# SCH_CarPCB_2023-11-15.net
KiCad netlist of a schematic drawn in EasyEDA
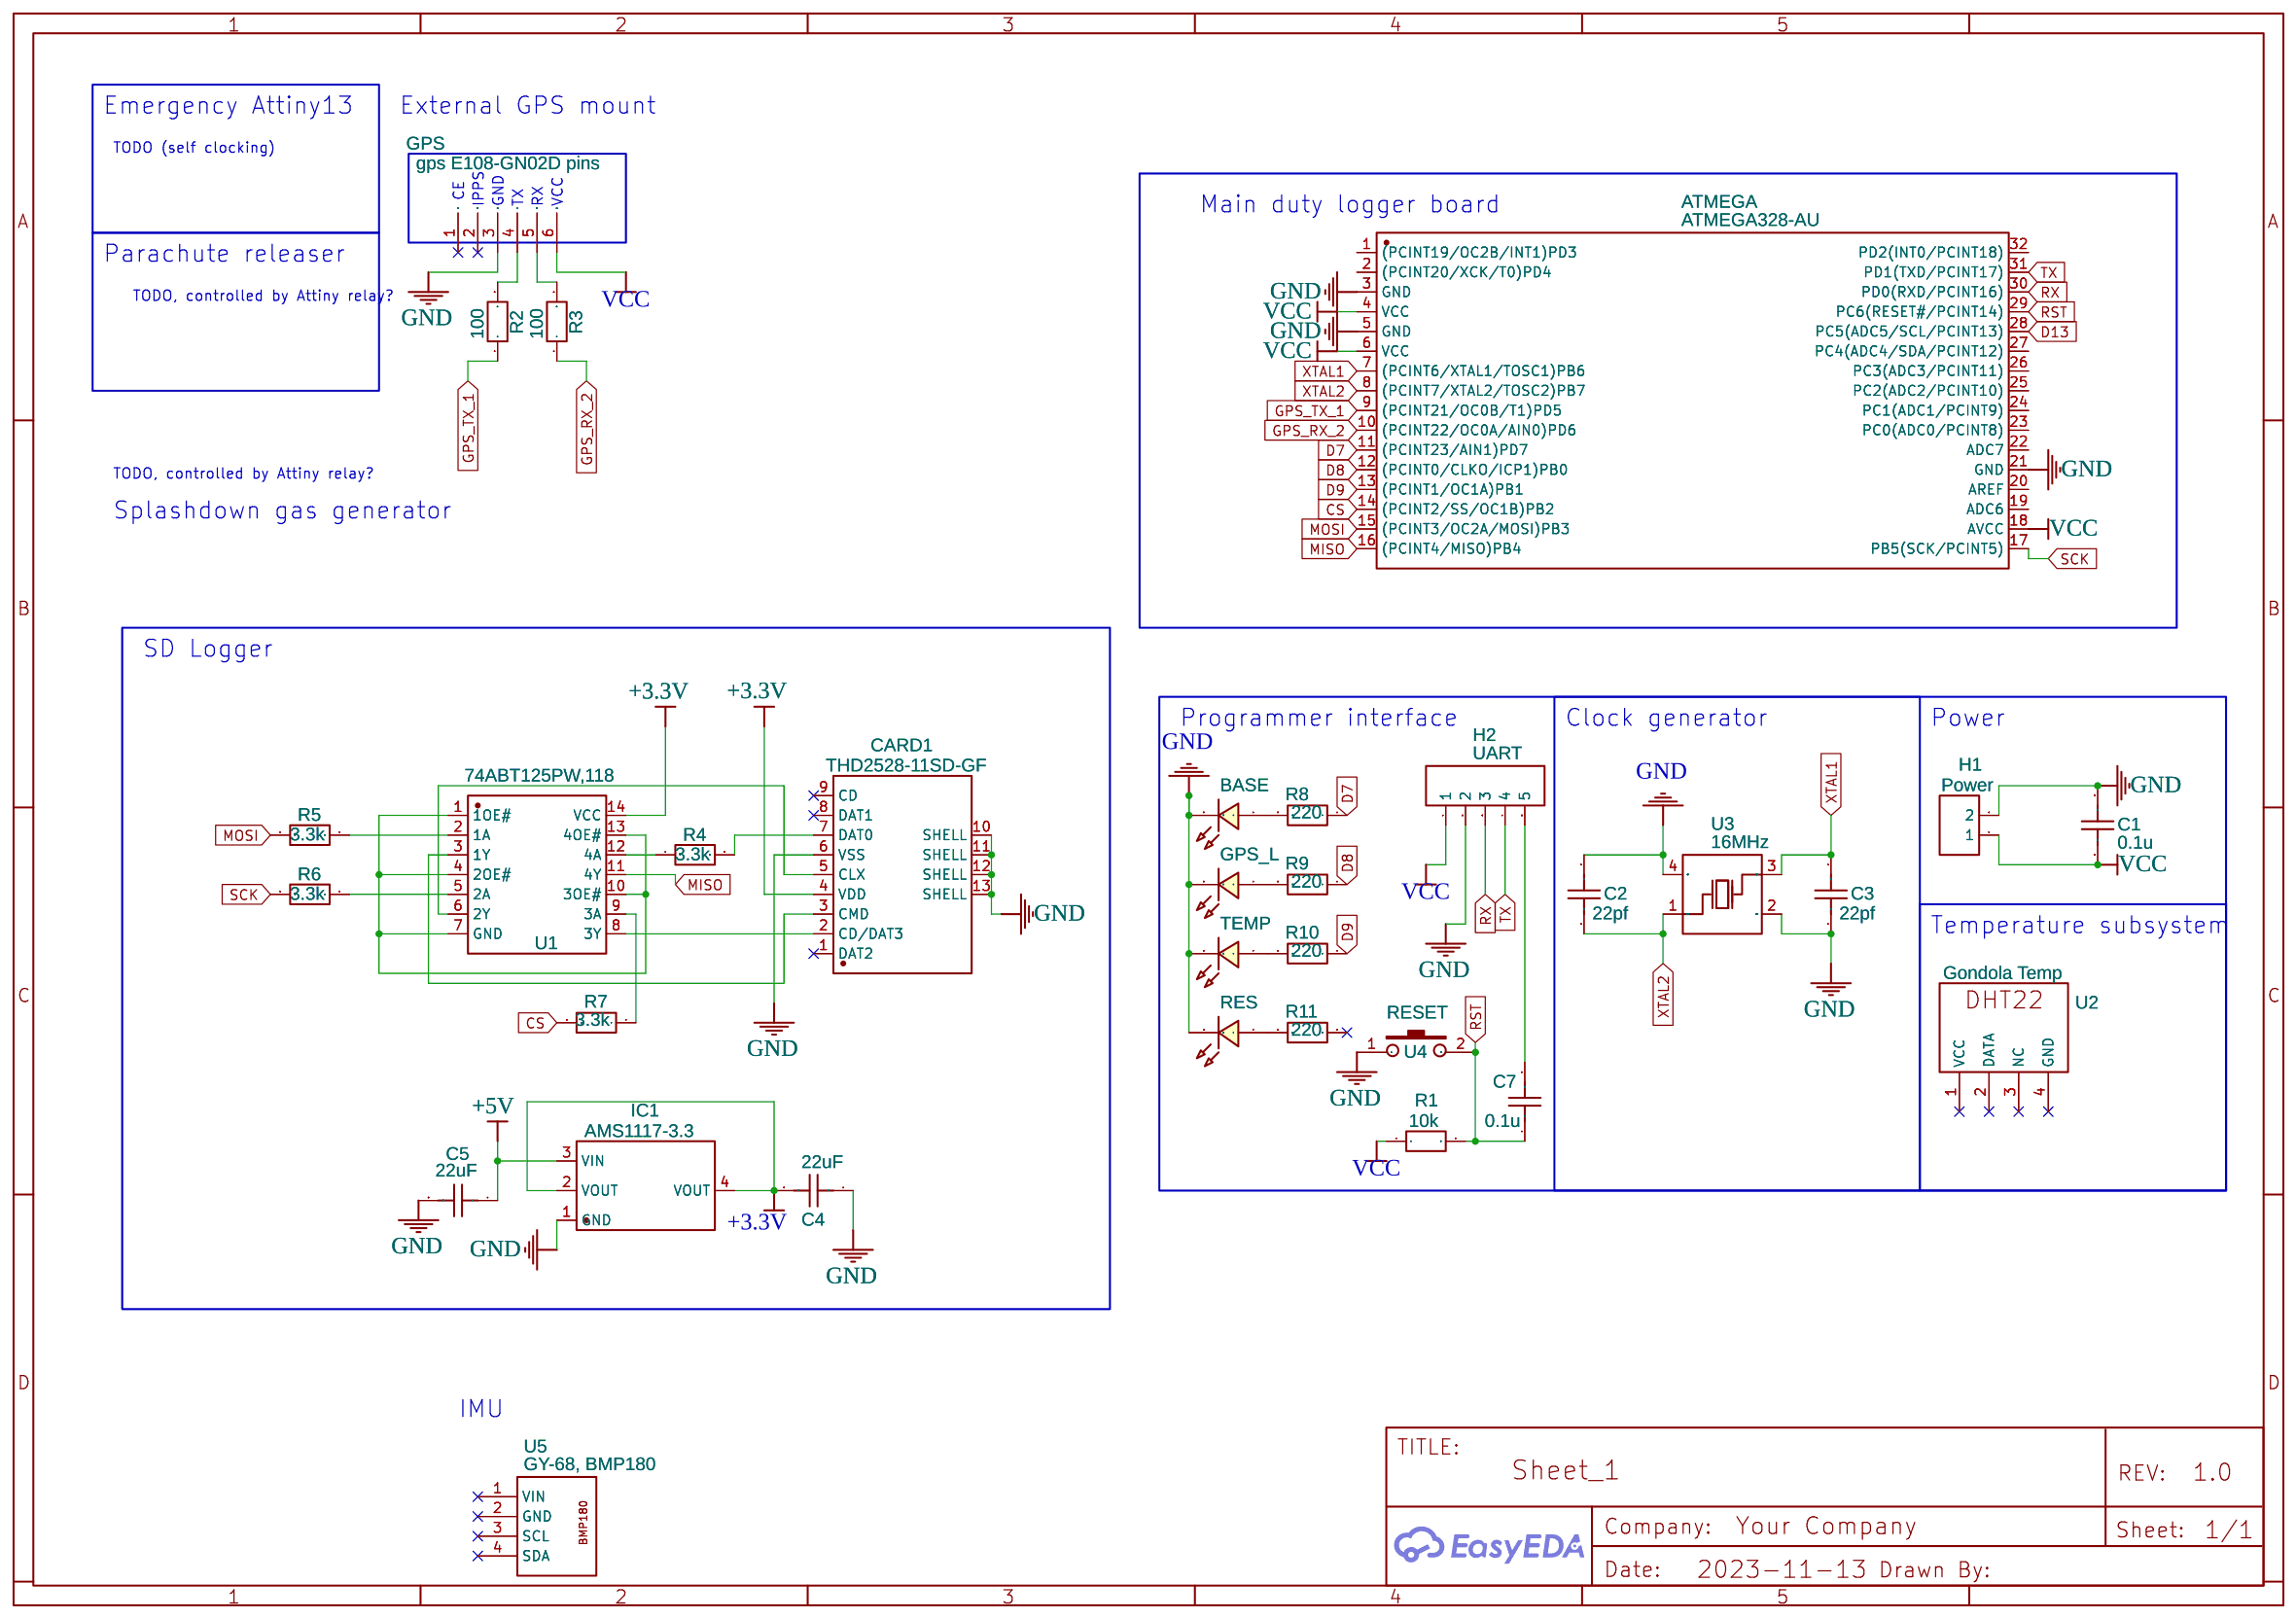
[diagram p0: schematic sheet]

(export (version "E")
  (design (tool "Eeschema 10.0.6"))
  (components
    (comp (ref "ATMEGA")
      (value "ATMEGA328-AU")
      (fields (field (name "Manufacturer") "MICROCHIP(美国微芯)"))
      (libsource (lib "") (part "ATMEGA328-AU"))
    )
    (comp (ref "BASE")
      (value "GPS")
      (fields
        (field (name "Manufacturer Part") "19-217/R6C-AL1M2VY/3T")
        (field (name "Manufacturer") "EVERLIGHT(台湾亿光)")
      )
      (libsource (lib "") (part "LED-0603_R_2"))
    )
    (comp (ref "C1") (value "0.1u") (libsource (lib "") (part "C_0603_US")))
    (comp (ref "C2") (value "22pf") (libsource (lib "") (part "C_0603_US")))
    (comp (ref "C3") (value "22pf") (libsource (lib "") (part "C_0603_US")))
    (comp (ref "C4") (value "22uF") (libsource (lib "") (part "C_0603_US_1")))
    (comp (ref "C5") (value "22uF") (libsource (lib "") (part "C_0603_US_1")))
    (comp (ref "C7") (value "0.1u") (libsource (lib "") (part "C_0603_US")))
    (comp (ref "CARD1")
      (value "THD2528-11SD-GF")
      (fields (field (name "Manufacturer") "THD"))
      (libsource (lib "") (part "THD2528-11SD-GF"))
    )
    (comp (ref "GPS")
      (value "gps E108-GN02D pins")
      (fields (field (name "Manufacturer Part") "New SchematicLib"))
      (libsource (lib "") (part "Header_6"))
    )
    (comp (ref "GPS_L")
      (value "GPS")
      (fields
        (field (name "Manufacturer Part") "19-217/R6C-AL1M2VY/3T")
        (field (name "Manufacturer") "EVERLIGHT(台湾亿光)")
      )
      (libsource (lib "") (part "LED-0603_R_1"))
    )
    (comp (ref "H1") (value "Power") (libsource (lib "") (part "HDR-F-2.54_1x2")))
    (comp (ref "H2") (value "UART") (libsource (lib "") (part "HDR-F-2.54_1x5")))
    (comp (ref "IC1") (value "AMS1117-3.3") (libsource (lib "") (part "AMS1117-3.3")))
    (comp (ref "R1") (value "10k") (libsource (lib "") (part "R_0603_EU_2")))
    (comp (ref "R2") (value "100") (libsource (lib "") (part "R_0603_EU_1")))
    (comp (ref "R3") (value "100") (libsource (lib "") (part "R_0603_EU_1")))
    (comp (ref "R4") (value "3.3k") (libsource (lib "") (part "R_0603_EU_2")))
    (comp (ref "R5") (value "3.3k") (libsource (lib "") (part "R_0603_EU")))
    (comp (ref "R6") (value "3.3k") (libsource (lib "") (part "R_0603_EU")))
    (comp (ref "R7") (value "3.3k") (libsource (lib "") (part "R_0603_EU")))
    (comp (ref "R8") (value "220") (libsource (lib "") (part "R_0603_EU")))
    (comp (ref "R9") (value "220") (libsource (lib "") (part "R_0603_EU")))
    (comp (ref "R10") (value "220") (libsource (lib "") (part "R_0603_EU")))
    (comp (ref "R11") (value "220") (libsource (lib "") (part "R_0603_EU")))
    (comp (ref "RES")
      (value "GPS")
      (fields
        (field (name "Manufacturer Part") "19-217/R6C-AL1M2VY/3T")
        (field (name "Manufacturer") "EVERLIGHT(台湾亿光)")
      )
      (libsource (lib "") (part "LED-0603_R"))
    )
    (comp (ref "TEMP")
      (value "GPS")
      (fields
        (field (name "Manufacturer Part") "19-217/R6C-AL1M2VY/3T")
        (field (name "Manufacturer") "EVERLIGHT(台湾亿光)")
      )
      (libsource (lib "") (part "LED-0603_R_3"))
    )
    (comp (ref "U1")
      (value "74ABT125PW,118")
      (fields (field (name "Manufacturer") "Nexperia"))
      (libsource (lib "") (part "74ABT125PW,118"))
    )
    (comp (ref "U2")
      (value "Gondola Temp")
      (fields (field (name "Manufacturer") "Aosong (Guangzhou) Electronics Co., Ltd."))
      (libsource (lib "") (part "DHT22"))
    )
    (comp (ref "U3")
      (value "16MHz")
      (fields
        (field (name "Manufacturer Part") "NX2520SA-16MHZ-STD-CSW-4")
        (field (name "Manufacturer") "NDK")
      )
      (libsource (lib "") (part "NX2520SA-16MHZ-STD-CSW-4"))
    )
    (comp (ref "U4")
      (value "RESET")
      (fields (field (name "Manufacturer Part") "key-2pinRESET"))
      (libsource (lib "") (part "KEY-2PINRESET"))
    )
    (comp (ref "U5")
      (value "GY-68, BMP180")
      (fields (field (name "Manufacturer Part") "BMP180"))
      (libsource (lib "") (part "GY-68, BMP180"))
    )
  )
  (nets
    (net (code "1") (name "+3.3V") (class "Default")
      (node (ref "C4") (pin "2") (pinfunction "2_2") (pintype "unspecified"))
      (node (ref "CARD1") (pin "4") (pinfunction "VDD_4") (pintype "unspecified"))
      (node (ref "IC1") (pin "2") (pinfunction "VOUT_2") (pintype "unspecified"))
      (node (ref "IC1") (pin "4") (pinfunction "VOUT_4") (pintype "unspecified"))
      (node (ref "U1") (pin "14") (pinfunction "VCC_14") (pintype "unspecified"))
    )
    (net (code "2") (name "+5V") (class "Default")
      (node (ref "C5") (pin "1") (pinfunction "1_1") (pintype "unspecified"))
      (node (ref "IC1") (pin "3") (pinfunction "VIN_3") (pintype "unspecified"))
    )
    (net (code "3") (name "CS") (class "Default")
      (node (ref "ATMEGA") (pin "14") (pinfunction "(PCINT2/SS/OC1B)PB2_14") (pintype "unspecified"))
      (node (ref "R7") (pin "2") (pinfunction "2_2") (pintype "unspecified"))
    )
    (net (code "4") (name "D7") (class "Default")
      (node (ref "ATMEGA") (pin "11") (pinfunction "(PCINT23/AIN1)PD7_11") (pintype "unspecified"))
      (node (ref "R8") (pin "1") (pinfunction "1_1") (pintype "unspecified"))
    )
    (net (code "5") (name "D8") (class "Default")
      (node (ref "ATMEGA") (pin "12") (pinfunction "(PCINT0/CLKO/ICP1)PB0_12") (pintype "unspecified"))
      (node (ref "R9") (pin "1") (pinfunction "1_1") (pintype "unspecified"))
    )
    (net (code "6") (name "D9") (class "Default")
      (node (ref "ATMEGA") (pin "13") (pinfunction "(PCINT1/OC1A)PB1_13") (pintype "unspecified"))
      (node (ref "R10") (pin "1") (pinfunction "1_1") (pintype "unspecified"))
    )
    (net (code "7") (name "D13") (class "Default")
      (node (ref "ATMEGA") (pin "28") (pinfunction "PC5(ADC5/SCL/PCINT13)_28") (pintype "unspecified"))
    )
    (net (code "8") (name "GND") (class "Default")
      (node (ref "ATMEGA") (pin "21") (pinfunction "GND_21") (pintype "unspecified"))
      (node (ref "ATMEGA") (pin "3") (pinfunction "GND_3") (pintype "unspecified"))
      (node (ref "ATMEGA") (pin "5") (pinfunction "GND_5") (pintype "unspecified"))
      (node (ref "BASE") (pin "2") (pinfunction "2_2") (pintype "unspecified"))
      (node (ref "C1") (pin "2") (pinfunction "2_2") (pintype "unspecified"))
      (node (ref "C2") (pin "2") (pinfunction "2_2") (pintype "unspecified"))
      (node (ref "C3") (pin "1") (pinfunction "1_1") (pintype "unspecified"))
      (node (ref "C4") (pin "1") (pinfunction "1_1") (pintype "unspecified"))
      (node (ref "C5") (pin "2") (pinfunction "2_2") (pintype "unspecified"))
      (node (ref "CARD1") (pin "10") (pinfunction "SHELL_10") (pintype "unspecified"))
      (node (ref "CARD1") (pin "11") (pinfunction "SHELL_11") (pintype "unspecified"))
      (node (ref "CARD1") (pin "12") (pinfunction "SHELL_12") (pintype "unspecified"))
      (node (ref "CARD1") (pin "13") (pinfunction "SHELL_13") (pintype "unspecified"))
      (node (ref "CARD1") (pin "6") (pinfunction "VSS_6") (pintype "unspecified"))
      (node (ref "GPS") (pin "3") (pinfunction "3_3") (pintype "unspecified"))
      (node (ref "GPS_L") (pin "2") (pinfunction "2_2") (pintype "unspecified"))
      (node (ref "H1") (pin "2") (pinfunction "2_2") (pintype "input"))
      (node (ref "H2") (pin "2") (pinfunction "2_2") (pintype "unspecified"))
      (node (ref "IC1") (pin "1") (pinfunction "GND_1") (pintype "unspecified"))
      (node (ref "RES") (pin "2") (pinfunction "2_2") (pintype "unspecified"))
      (node (ref "TEMP") (pin "2") (pinfunction "2_2") (pintype "unspecified"))
      (node (ref "U3") (pin "2") (pinfunction "GND_2") (pintype "unspecified"))
      (node (ref "U3") (pin "4") (pinfunction "GND_4") (pintype "unspecified"))
      (node (ref "U4") (pin "1") (pinfunction "1_1") (pintype "unspecified"))
    )
    (net (code "9") (name "GPS_RX_2") (class "Default")
      (node (ref "ATMEGA") (pin "10") (pinfunction "(PCINT22/OC0A/AIN0)PD6_10") (pintype "unspecified"))
      (node (ref "R3") (pin "1") (pinfunction "1_1") (pintype "unspecified"))
    )
    (net (code "10") (name "GPS_TX_1") (class "Default")
      (node (ref "ATMEGA") (pin "9") (pinfunction "(PCINT21/OC0B/T1)PD5_9") (pintype "unspecified"))
      (node (ref "R2") (pin "1") (pinfunction "1_1") (pintype "unspecified"))
    )
    (net (code "11") (name "MISO") (class "Default")
      (node (ref "ATMEGA") (pin "16") (pinfunction "(PCINT4/MISO)PB4_16") (pintype "unspecified"))
      (node (ref "U1") (pin "11") (pinfunction "4Y_11") (pintype "unspecified"))
    )
    (net (code "12") (name "MOSI") (class "Default")
      (node (ref "ATMEGA") (pin "15") (pinfunction "(PCINT3/OC2A/MOSI)PB3_15") (pintype "unspecified"))
      (node (ref "R5") (pin "2") (pinfunction "2_2") (pintype "unspecified"))
    )
    (net (code "13") (name "Net-(BASE-Pad1)") (class "Default")
      (node (ref "BASE") (pin "1") (pinfunction "1_1") (pintype "unspecified"))
      (node (ref "R8") (pin "2") (pinfunction "2_2") (pintype "unspecified"))
    )
    (net (code "14") (name "Net-(C7-Pad2)") (class "Default")
      (node (ref "C7") (pin "2") (pinfunction "2_2") (pintype "unspecified"))
      (node (ref "H2") (pin "5") (pinfunction "5_5") (pintype "unspecified"))
    )
    (net (code "15") (name "Net-(CARD1-CD{slash}DAT3)") (class "Default")
      (node (ref "CARD1") (pin "2") (pinfunction "CD/DAT3_2") (pintype "unspecified"))
      (node (ref "U1") (pin "8") (pinfunction "3Y_8") (pintype "unspecified"))
    )
    (net (code "16") (name "Net-(CARD1-CLX)") (class "Default")
      (node (ref "CARD1") (pin "5") (pinfunction "CLX_5") (pintype "unspecified"))
      (node (ref "U1") (pin "6") (pinfunction "2Y_6") (pintype "unspecified"))
    )
    (net (code "17") (name "Net-(CARD1-CMD)") (class "Default")
      (node (ref "CARD1") (pin "3") (pinfunction "CMD_3") (pintype "unspecified"))
      (node (ref "U1") (pin "3") (pinfunction "1Y_3") (pintype "unspecified"))
    )
    (net (code "18") (name "Net-(CARD1-DAT0)") (class "Default")
      (node (ref "CARD1") (pin "7") (pinfunction "DAT0_7") (pintype "unspecified"))
      (node (ref "R4") (pin "2") (pinfunction "2_2") (pintype "unspecified"))
    )
    (net (code "19") (name "Net-(GPS-Pad4)") (class "Default")
      (node (ref "GPS") (pin "4") (pinfunction "4_4") (pintype "unspecified"))
      (node (ref "R2") (pin "2") (pinfunction "2_2") (pintype "unspecified"))
    )
    (net (code "20") (name "Net-(GPS-Pad5)") (class "Default")
      (node (ref "GPS") (pin "5") (pinfunction "5_5") (pintype "unspecified"))
      (node (ref "R3") (pin "2") (pinfunction "2_2") (pintype "unspecified"))
    )
    (net (code "21") (name "Net-(GPS_L-Pad1)") (class "Default")
      (node (ref "GPS_L") (pin "1") (pinfunction "1_1") (pintype "unspecified"))
      (node (ref "R9") (pin "2") (pinfunction "2_2") (pintype "unspecified"))
    )
    (net (code "22") (name "Net-(R10-Pad2)") (class "Default")
      (node (ref "R10") (pin "2") (pinfunction "2_2") (pintype "unspecified"))
      (node (ref "TEMP") (pin "1") (pinfunction "1_1") (pintype "unspecified"))
    )
    (net (code "23") (name "Net-(R11-Pad2)") (class "Default")
      (node (ref "R11") (pin "2") (pinfunction "2_2") (pintype "unspecified"))
      (node (ref "RES") (pin "1") (pinfunction "1_1") (pintype "unspecified"))
    )
    (net (code "24") (name "Net-(U1-1A)") (class "Default")
      (node (ref "R5") (pin "1") (pinfunction "1_1") (pintype "unspecified"))
      (node (ref "U1") (pin "2") (pinfunction "1A_2") (pintype "unspecified"))
    )
    (net (code "25") (name "Net-(U1-1OE#)") (class "Default")
      (node (ref "U1") (pin "1") (pinfunction "1OE#_1") (pintype "unspecified"))
      (node (ref "U1") (pin "10") (pinfunction "3OE#_10") (pintype "unspecified"))
      (node (ref "U1") (pin "13") (pinfunction "4OE#_13") (pintype "unspecified"))
      (node (ref "U1") (pin "4") (pinfunction "2OE#_4") (pintype "unspecified"))
      (node (ref "U1") (pin "7") (pinfunction "GND_7") (pintype "unspecified"))
    )
    (net (code "26") (name "Net-(U1-2A)") (class "Default")
      (node (ref "R6") (pin "1") (pinfunction "1_1") (pintype "unspecified"))
      (node (ref "U1") (pin "5") (pinfunction "2A_5") (pintype "unspecified"))
    )
    (net (code "27") (name "Net-(U1-3A)") (class "Default")
      (node (ref "R7") (pin "1") (pinfunction "1_1") (pintype "unspecified"))
      (node (ref "U1") (pin "9") (pinfunction "3A_9") (pintype "unspecified"))
    )
    (net (code "28") (name "Net-(U1-4A)") (class "Default")
      (node (ref "R4") (pin "1") (pinfunction "1_1") (pintype "unspecified"))
      (node (ref "U1") (pin "12") (pinfunction "4A_12") (pintype "unspecified"))
    )
    (net (code "29") (name "RST") (class "Default")
      (node (ref "ATMEGA") (pin "29") (pinfunction "PC6(RESET#/PCINT14)_29") (pintype "unspecified"))
      (node (ref "C7") (pin "1") (pinfunction "1_1") (pintype "unspecified"))
      (node (ref "R1") (pin "2") (pinfunction "2_2") (pintype "unspecified"))
      (node (ref "U4") (pin "2") (pinfunction "2_2") (pintype "unspecified"))
    )
    (net (code "30") (name "RX") (class "Default")
      (node (ref "ATMEGA") (pin "30") (pinfunction "PD0(RXD/PCINT16)_30") (pintype "unspecified"))
      (node (ref "H2") (pin "3") (pinfunction "3_3") (pintype "unspecified"))
    )
    (net (code "31") (name "SCK") (class "Default")
      (node (ref "ATMEGA") (pin "17") (pinfunction "PB5(SCK/PCINT5)_17") (pintype "unspecified"))
      (node (ref "R6") (pin "2") (pinfunction "2_2") (pintype "unspecified"))
    )
    (net (code "32") (name "TX") (class "Default")
      (node (ref "ATMEGA") (pin "31") (pinfunction "PD1(TXD/PCINT17)_31") (pintype "unspecified"))
      (node (ref "H2") (pin "4") (pinfunction "4_4") (pintype "unspecified"))
    )
    (net (code "33") (name "VCC") (class "Default")
      (node (ref "ATMEGA") (pin "18") (pinfunction "AVCC_18") (pintype "unspecified"))
      (node (ref "ATMEGA") (pin "4") (pinfunction "VCC_4") (pintype "unspecified"))
      (node (ref "ATMEGA") (pin "6") (pinfunction "VCC_6") (pintype "unspecified"))
      (node (ref "C1") (pin "1") (pinfunction "1_1") (pintype "unspecified"))
      (node (ref "GPS") (pin "6") (pinfunction "6_6") (pintype "unspecified"))
      (node (ref "H1") (pin "1") (pinfunction "1_1") (pintype "input"))
      (node (ref "H2") (pin "1") (pinfunction "1_1") (pintype "unspecified"))
      (node (ref "R1") (pin "1") (pinfunction "1_1") (pintype "unspecified"))
    )
    (net (code "34") (name "XTAL1") (class "Default")
      (node (ref "ATMEGA") (pin "7") (pinfunction "(PCINT6/XTAL1/TOSC1)PB6_7") (pintype "unspecified"))
      (node (ref "C3") (pin "2") (pinfunction "2_2") (pintype "unspecified"))
      (node (ref "U3") (pin "3") (pinfunction "OSC2_3") (pintype "unspecified"))
    )
    (net (code "35") (name "XTAL2") (class "Default")
      (node (ref "ATMEGA") (pin "8") (pinfunction "(PCINT7/XTAL2/TOSC2)PB7_8") (pintype "unspecified"))
      (node (ref "C2") (pin "1") (pinfunction "1_1") (pintype "unspecified"))
      (node (ref "U3") (pin "1") (pinfunction "OSC1_1") (pintype "unspecified"))
    )
    (net (code "36") (name "unconnected-(ATMEGA-(PCINT19{slash}OC2B{slash}INT1)PD3-Pad1)") (class "Default")
      (node (ref "ATMEGA") (pin "1") (pinfunction "(PCINT19/OC2B/INT1)PD3_1") (pintype "unspecified"))
    )
    (net (code "37") (name "unconnected-(ATMEGA-(PCINT20{slash}XCK{slash}T0)PD4-Pad2)") (class "Default")
      (node (ref "ATMEGA") (pin "2") (pinfunction "(PCINT20/XCK/T0)PD4_2") (pintype "unspecified"))
    )
    (net (code "38") (name "unconnected-(ATMEGA-ADC6-Pad19)") (class "Default")
      (node (ref "ATMEGA") (pin "19") (pinfunction "ADC6_19") (pintype "unspecified"))
    )
    (net (code "39") (name "unconnected-(ATMEGA-ADC7-Pad22)") (class "Default")
      (node (ref "ATMEGA") (pin "22") (pinfunction "ADC7_22") (pintype "unspecified"))
    )
    (net (code "40") (name "unconnected-(ATMEGA-AREF-Pad20)") (class "Default")
      (node (ref "ATMEGA") (pin "20") (pinfunction "AREF_20") (pintype "unspecified"))
    )
    (net (code "41") (name "unconnected-(ATMEGA-PC0(ADC0{slash}PCINT8)-Pad23)") (class "Default")
      (node (ref "ATMEGA") (pin "23") (pinfunction "PC0(ADC0/PCINT8)_23") (pintype "unspecified"))
    )
    (net (code "42") (name "unconnected-(ATMEGA-PC1(ADC1{slash}PCINT9)-Pad24)") (class "Default")
      (node (ref "ATMEGA") (pin "24") (pinfunction "PC1(ADC1/PCINT9)_24") (pintype "unspecified"))
    )
    (net (code "43") (name "unconnected-(ATMEGA-PC2(ADC2{slash}PCINT10)-Pad25)") (class "Default")
      (node (ref "ATMEGA") (pin "25") (pinfunction "PC2(ADC2/PCINT10)_25") (pintype "unspecified"))
    )
    (net (code "44") (name "unconnected-(ATMEGA-PC3(ADC3{slash}PCINT11)-Pad26)") (class "Default")
      (node (ref "ATMEGA") (pin "26") (pinfunction "PC3(ADC3/PCINT11)_26") (pintype "unspecified"))
    )
    (net (code "45") (name "unconnected-(ATMEGA-PC4(ADC4{slash}SDA{slash}PCINT12)-Pad27)") (class "Default")
      (node (ref "ATMEGA") (pin "27") (pinfunction "PC4(ADC4/SDA/PCINT12)_27") (pintype "unspecified"))
    )
    (net (code "46") (name "unconnected-(ATMEGA-PD2(INT0{slash}PCINT18)-Pad32)") (class "Default")
      (node (ref "ATMEGA") (pin "32") (pinfunction "PD2(INT0/PCINT18)_32") (pintype "unspecified"))
    )
    (net (code "47") (name "unconnected-(CARD1-CD-Pad9)") (class "Default")
      (node (ref "CARD1") (pin "9") (pinfunction "CD_9") (pintype "unspecified+no_connect"))
    )
    (net (code "48") (name "unconnected-(CARD1-DAT1-Pad8)") (class "Default")
      (node (ref "CARD1") (pin "8") (pinfunction "DAT1_8") (pintype "unspecified+no_connect"))
    )
    (net (code "49") (name "unconnected-(CARD1-DAT2-Pad1)") (class "Default")
      (node (ref "CARD1") (pin "1") (pinfunction "DAT2_1") (pintype "unspecified+no_connect"))
    )
    (net (code "50") (name "unconnected-(GPS-Pad1)") (class "Default")
      (node (ref "GPS") (pin "1") (pinfunction "1_1") (pintype "unspecified+no_connect"))
    )
    (net (code "51") (name "unconnected-(GPS-Pad2)") (class "Default")
      (node (ref "GPS") (pin "2") (pinfunction "2_2") (pintype "unspecified+no_connect"))
    )
    (net (code "52") (name "unconnected-(R11-Pad1)") (class "Default")
      (node (ref "R11") (pin "1") (pinfunction "1_1") (pintype "unspecified+no_connect"))
    )
    (net (code "53") (name "unconnected-(U2-DATA-Pad2)") (class "Default")
      (node (ref "U2") (pin "2") (pinfunction "DATA_2") (pintype "unspecified+no_connect"))
    )
    (net (code "54") (name "unconnected-(U2-GND-Pad4)") (class "Default")
      (node (ref "U2") (pin "4") (pinfunction "GND_4") (pintype "unspecified+no_connect"))
    )
    (net (code "55") (name "unconnected-(U2-NC-Pad3)") (class "Default")
      (node (ref "U2") (pin "3") (pinfunction "NC_3") (pintype "unspecified+no_connect"))
    )
    (net (code "56") (name "unconnected-(U2-VCC-Pad1)") (class "Default")
      (node (ref "U2") (pin "1") (pinfunction "VCC_1") (pintype "unspecified+no_connect"))
    )
    (net (code "57") (name "unconnected-(U5-GND-Pad2)") (class "Default")
      (node (ref "U5") (pin "2") (pinfunction "GND_2") (pintype "unspecified+no_connect"))
    )
    (net (code "58") (name "unconnected-(U5-SCL-Pad3)") (class "Default")
      (node (ref "U5") (pin "3") (pinfunction "SCL_3") (pintype "unspecified+no_connect"))
    )
    (net (code "59") (name "unconnected-(U5-SDA-Pad4)") (class "Default")
      (node (ref "U5") (pin "4") (pinfunction "SDA_4") (pintype "unspecified+no_connect"))
    )
    (net (code "60") (name "unconnected-(U5-VIN-Pad1)") (class "Default")
      (node (ref "U5") (pin "1") (pinfunction "VIN_1") (pintype "unspecified+no_connect"))
    )
  )
)
